# EasyEDA-SCH_IoT-Indoor-Climate-Sensor-up.net
KiCad netlist of a schematic drawn in EasyEDA
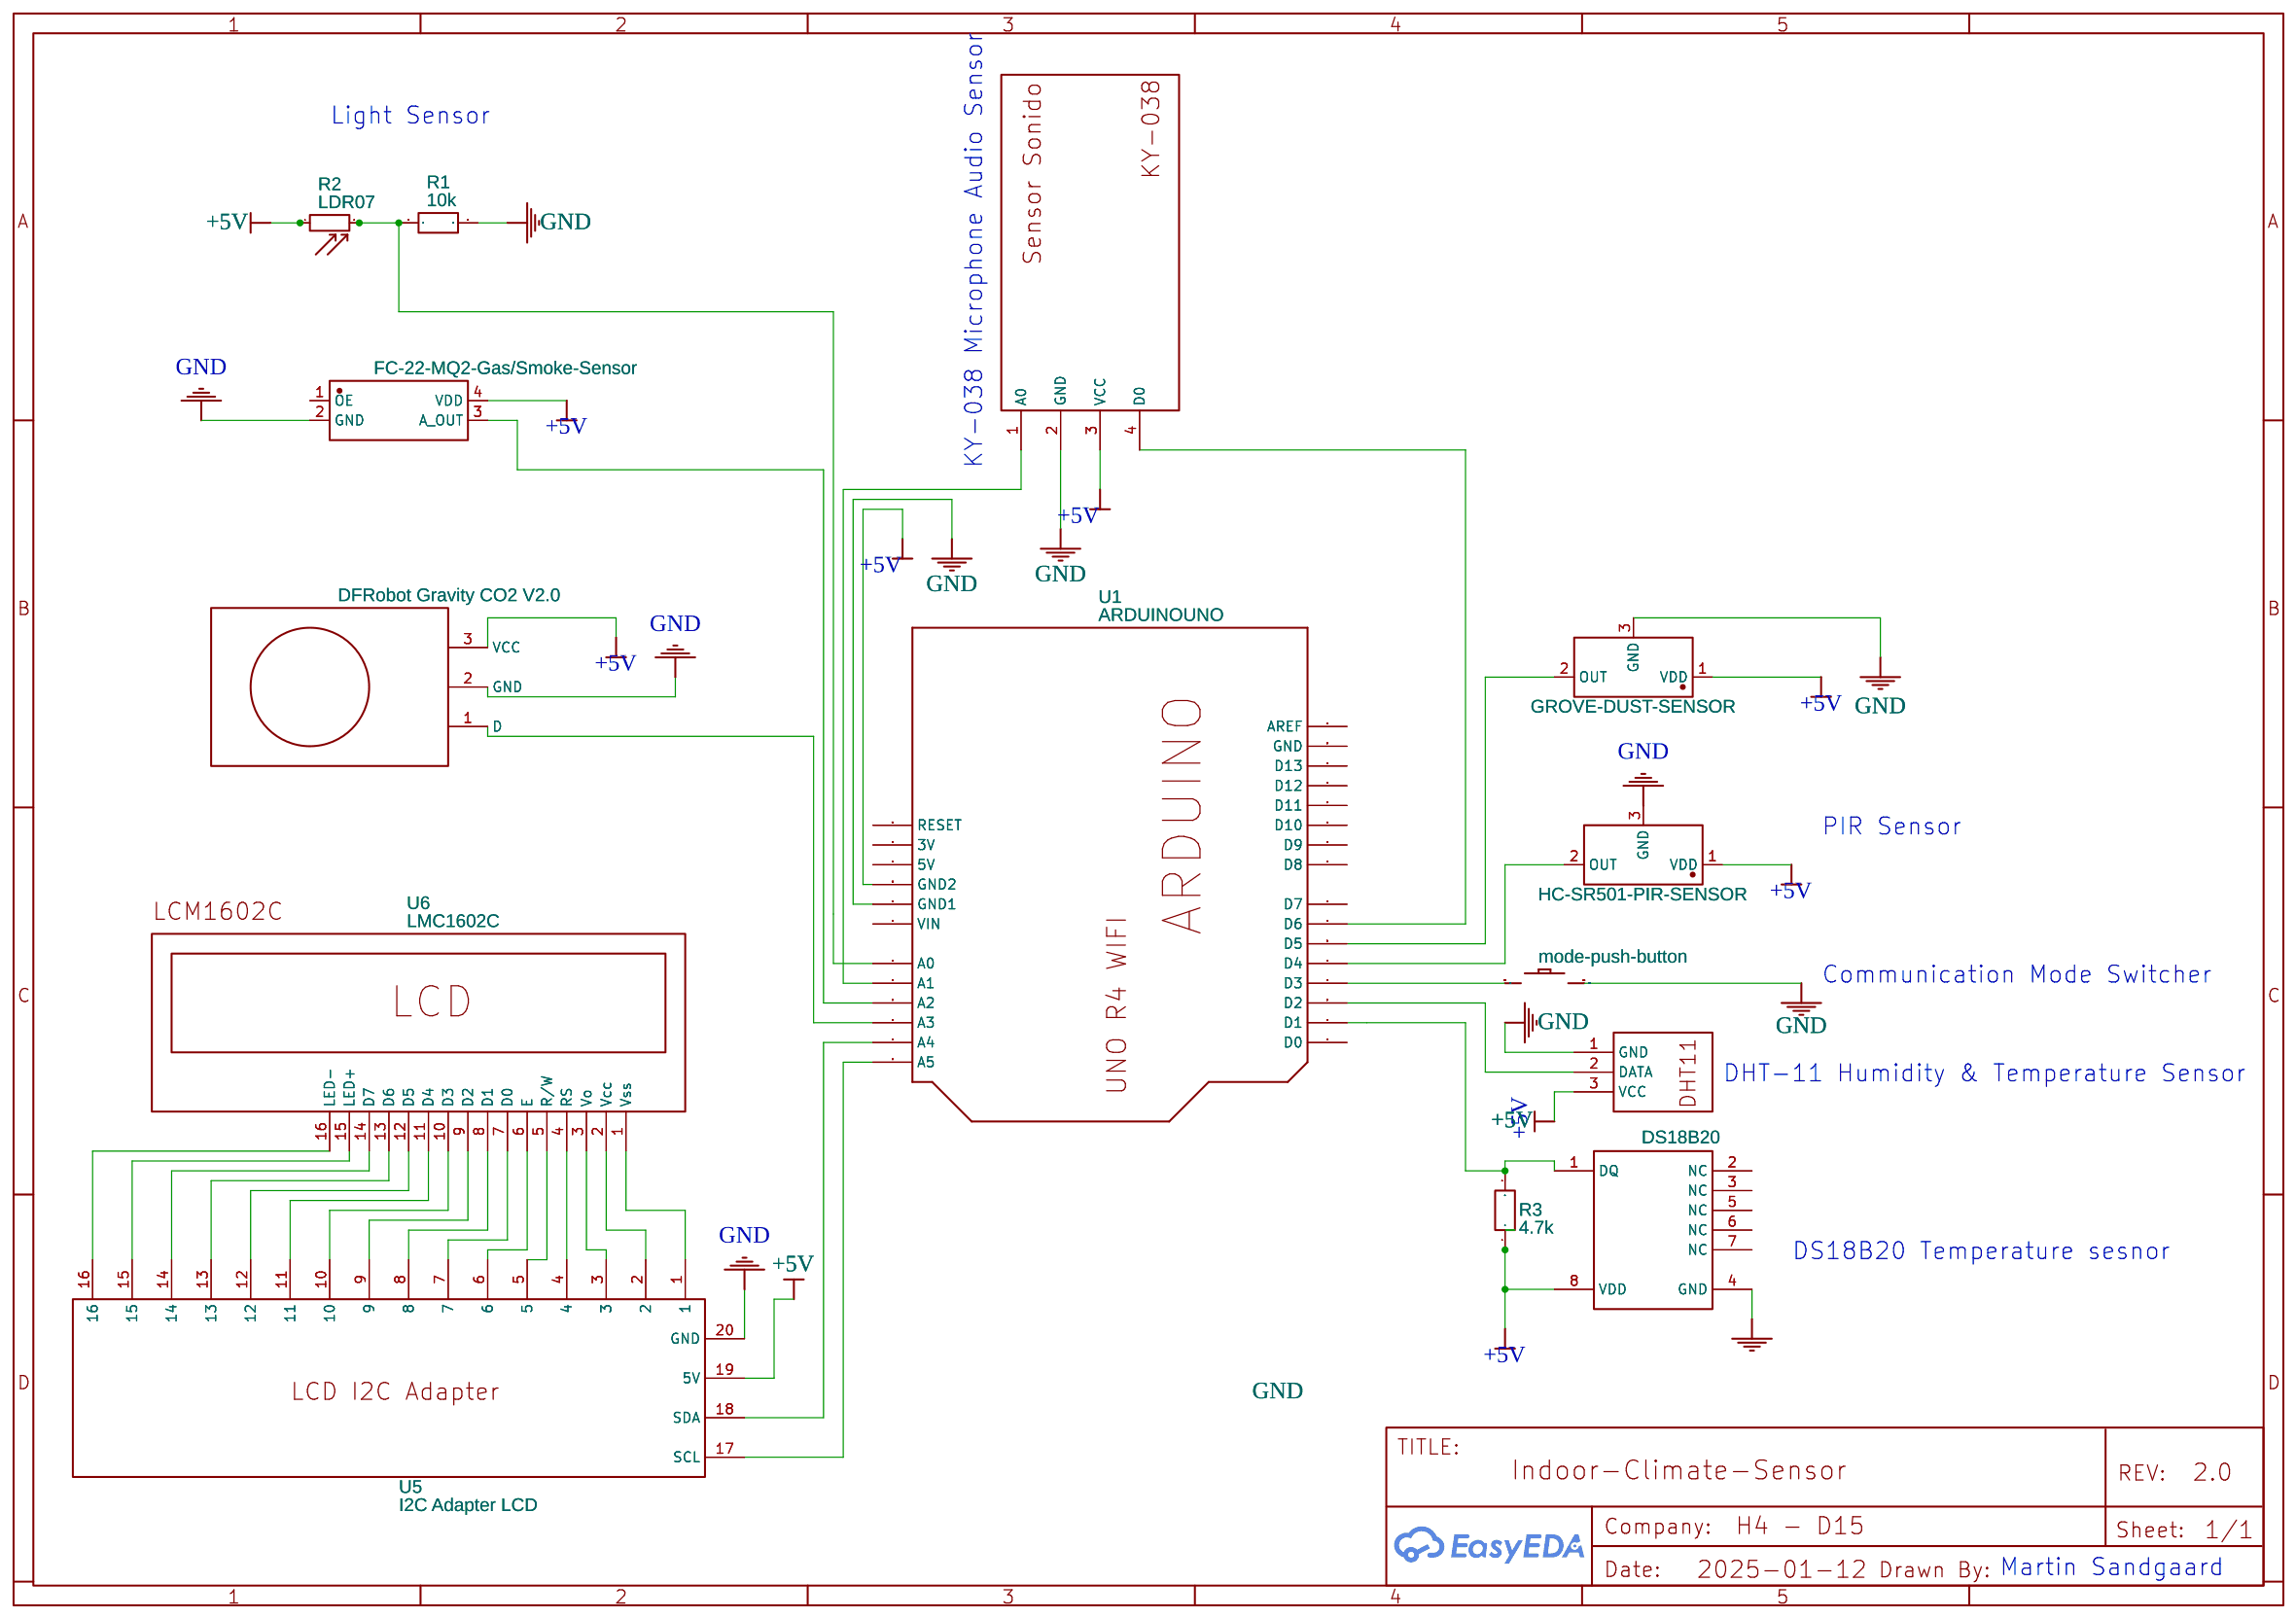
[diagram p0: schematic sheet]

(export (version "E")
  (design (tool "Eeschema 10.0.6"))
  (components
    (comp (ref "1") (value "mode-push-button") (libsource (lib "") (part "button")))
    (comp (ref "GROVE-DUST-SENSOR")
      (value "EKMB1309113K")
      (fields (field (name "Manufacturer") "PANASONIC(松下)"))
      (libsource (lib "") (part "EKMB1309113K_1"))
    )
    (comp (ref "HC-SR501-PIR-SENSOR")
      (value "EKMB1309113K")
      (fields (field (name "Manufacturer") "PANASONIC(松下)"))
      (libsource (lib "") (part "EKMB1309113K"))
    )
    (comp (ref "OSC1")
      (value "FC-22-MQ2-Gas/Smoke-Sensor")
      (fields (field (name "Manufacturer Part") "AMPMDFC-22.0000T3") (field (name "Manufacturer") "ABRACON"))
      (libsource (lib "") (part "AMPMDFC-22.0000T3"))
    )
    (comp (ref "R1") (value "10k") (libsource (lib "") (part "R_0603_EU_1")))
    (comp (ref "R2") (value "LDR07") (libsource (lib "") (part "LDR07")))
    (comp (ref "R3") (value "4.7k") (libsource (lib "") (part "R_0603_EU")))
    (comp (ref "U1") (value "ARDUINOUNO") (libsource (lib "") (part "ARDUINOUNO")))
    (comp (ref "U2") (value "DS18B20") (libsource (lib "") (part "DS18B20U+")))
    (comp (ref "U3")
      (value "KY-038 Microphone Sound Sensor")
      (libsource (lib "") (part "KY-037 KY038 SENSOR SONIDO COPY"))
    )
    (comp (ref "U4") (value "DHT-11") (libsource (lib "") (part "DHT-11")))
    (comp (ref "U5") (value "I2C Adapter LCD") (libsource (lib "") (part "I2C Adapter LCD")))
    (comp (ref "U6") (value "LMC1602C") (libsource (lib "") (part "LMC1602C")))
    (comp (ref "U7")
      (value "DFRobot Gravity CO2 V2.0")
      (libsource (lib "") (part "DFRobot Gravity - czujnik dwutlenku węgla CO2 - elektrochemiczny"))
    )
  )
  (nets
    (net (code "1") (name "+5V") (class "Default")
      (node (ref "GROVE-DUST-SENSOR") (pin "1") (pinfunction "VDD_1") (pintype "unspecified"))
      (node (ref "HC-SR501-PIR-SENSOR") (pin "1") (pinfunction "VDD_1") (pintype "unspecified"))
      (node (ref "OSC1") (pin "4") (pinfunction "VDD_4") (pintype "unspecified"))
      (node (ref "R2") (pin "1") (pintype "unspecified"))
      (node (ref "R3") (pin "1") (pinfunction "1_1") (pintype "unspecified"))
      (node (ref "U1") (pin "GND2") (pinfunction "GND2_GND2") (pintype "passive"))
      (node (ref "U2") (pin "8") (pinfunction "VDD_8") (pintype "passive"))
      (node (ref "U3") (pin "3") (pinfunction "VCC_3") (pintype "unspecified"))
      (node (ref "U4") (pin "3") (pinfunction "VCC_3") (pintype "unspecified"))
      (node (ref "U5") (pin "19") (pinfunction "5V_19") (pintype "unspecified"))
    )
    (net (code "2") (name "GND") (class "Default")
      (node (ref "1") (pin "P$ACTIVE") (pinfunction "P$ACTIVE_P$ACTIVE") (pintype "unspecified"))
      (node (ref "GROVE-DUST-SENSOR") (pin "3") (pinfunction "GND_3") (pintype "unspecified"))
      (node (ref "HC-SR501-PIR-SENSOR") (pin "3") (pinfunction "GND_3") (pintype "unspecified"))
      (node (ref "OSC1") (pin "2") (pinfunction "GND_2") (pintype "unspecified"))
      (node (ref "R1") (pin "1") (pinfunction "1_1") (pintype "unspecified"))
      (node (ref "U1") (pin "GND1") (pinfunction "GND1_GND1") (pintype "passive"))
      (node (ref "U2") (pin "4") (pinfunction "GND_4") (pintype "passive"))
      (node (ref "U3") (pin "2") (pinfunction "GND_2") (pintype "unspecified"))
      (node (ref "U4") (pin "1") (pinfunction "GND_1") (pintype "unspecified"))
      (node (ref "U5") (pin "20") (pinfunction "GND_20") (pintype "unspecified"))
    )
    (net (code "3") (name "Net-(1-PadP$GND)") (class "Default")
      (node (ref "1") (pin "P$GND") (pinfunction "P$GND_P$GND") (pintype "unspecified"))
      (node (ref "U1") (pin "D3") (pinfunction "D3_D3") (pintype "unspecified"))
    )
    (net (code "4") (name "Net-(GROVE-DUST-SENSOR-OUT)") (class "Default")
      (node (ref "GROVE-DUST-SENSOR") (pin "2") (pinfunction "OUT_2") (pintype "unspecified"))
      (node (ref "U1") (pin "D5") (pinfunction "D5_D5") (pintype "unspecified"))
    )
    (net (code "5") (name "Net-(HC-SR501-PIR-SENSOR-OUT)") (class "Default")
      (node (ref "HC-SR501-PIR-SENSOR") (pin "2") (pinfunction "OUT_2") (pintype "unspecified"))
      (node (ref "U1") (pin "D4") (pinfunction "D4_D4") (pintype "unspecified"))
    )
    (net (code "6") (name "Net-(OSC1-A_OUT)") (class "Default")
      (node (ref "OSC1") (pin "3") (pinfunction "A_OUT_3") (pintype "unspecified"))
      (node (ref "U1") (pin "A2") (pinfunction "A2_A2") (pintype "unspecified"))
    )
    (net (code "7") (name "Net-(R1-Pad2)") (class "Default")
      (node (ref "R1") (pin "2") (pinfunction "2_2") (pintype "unspecified"))
      (node (ref "R2") (pin "2") (pintype "unspecified"))
      (node (ref "U1") (pin "A0") (pinfunction "A0_A0") (pintype "unspecified"))
    )
    (net (code "8") (name "Net-(U2-DQ)") (class "Default")
      (node (ref "R3") (pin "2") (pinfunction "2_2") (pintype "unspecified"))
      (node (ref "U1") (pin "D1") (pinfunction "D1_D1") (pintype "unspecified"))
      (node (ref "U2") (pin "1") (pinfunction "DQ_1") (pintype "bidirectional"))
    )
    (net (code "9") (name "Net-(U3-A0)") (class "Default")
      (node (ref "U1") (pin "A1") (pinfunction "A1_A1") (pintype "unspecified"))
      (node (ref "U3") (pin "1") (pinfunction "A0_1") (pintype "unspecified"))
    )
    (net (code "10") (name "Net-(U3-D0)") (class "Default")
      (node (ref "U1") (pin "D6") (pinfunction "D6_D6") (pintype "unspecified"))
      (node (ref "U3") (pin "4") (pinfunction "D0_4") (pintype "unspecified"))
    )
    (net (code "11") (name "Net-(U4-DATA)") (class "Default")
      (node (ref "U1") (pin "D2") (pinfunction "D2_D2") (pintype "unspecified"))
      (node (ref "U4") (pin "2") (pinfunction "DATA_2") (pintype "unspecified"))
    )
    (net (code "12") (name "Net-(U5-SCL)") (class "Default")
      (node (ref "U1") (pin "A5") (pinfunction "A5_A5") (pintype "unspecified"))
      (node (ref "U5") (pin "17") (pinfunction "SCL_17") (pintype "unspecified"))
    )
    (net (code "13") (name "Net-(U5-SDA)") (class "Default")
      (node (ref "U1") (pin "A4") (pinfunction "A4_A4") (pintype "unspecified"))
      (node (ref "U5") (pin "18") (pinfunction "SDA_18") (pintype "unspecified"))
    )
    (net (code "14") (name "Net-(U6-D0)") (class "Default")
      (node (ref "U5") (pin "7") (pinfunction "7_7") (pintype "unspecified"))
      (node (ref "U6") (pin "7") (pinfunction "D0_7") (pintype "unspecified"))
    )
    (net (code "15") (name "Net-(U6-D1)") (class "Default")
      (node (ref "U5") (pin "8") (pinfunction "8_8") (pintype "unspecified"))
      (node (ref "U6") (pin "8") (pinfunction "D1_8") (pintype "unspecified"))
    )
    (net (code "16") (name "Net-(U6-D2)") (class "Default")
      (node (ref "U5") (pin "9") (pinfunction "9_9") (pintype "unspecified"))
      (node (ref "U6") (pin "9") (pinfunction "D2_9") (pintype "unspecified"))
    )
    (net (code "17") (name "Net-(U6-D3)") (class "Default")
      (node (ref "U5") (pin "10") (pinfunction "10_10") (pintype "unspecified"))
      (node (ref "U6") (pin "10") (pinfunction "D3_10") (pintype "unspecified"))
    )
    (net (code "18") (name "Net-(U6-D4)") (class "Default")
      (node (ref "U5") (pin "11") (pinfunction "11_11") (pintype "unspecified"))
      (node (ref "U6") (pin "11") (pinfunction "D4_11") (pintype "unspecified"))
    )
    (net (code "19") (name "Net-(U6-D5)") (class "Default")
      (node (ref "U5") (pin "12") (pinfunction "12_12") (pintype "unspecified"))
      (node (ref "U6") (pin "12") (pinfunction "D5_12") (pintype "unspecified"))
    )
    (net (code "20") (name "Net-(U6-D6)") (class "Default")
      (node (ref "U5") (pin "13") (pinfunction "13_13") (pintype "unspecified"))
      (node (ref "U6") (pin "13") (pinfunction "D6_13") (pintype "unspecified"))
    )
    (net (code "21") (name "Net-(U6-D7)") (class "Default")
      (node (ref "U5") (pin "14") (pinfunction "14_14") (pintype "unspecified"))
      (node (ref "U6") (pin "14") (pinfunction "D7_14") (pintype "unspecified"))
    )
    (net (code "22") (name "Net-(U6-E)") (class "Default")
      (node (ref "U5") (pin "6") (pinfunction "6_6") (pintype "unspecified"))
      (node (ref "U6") (pin "6") (pinfunction "E_6") (pintype "unspecified"))
    )
    (net (code "23") (name "Net-(U6-LED+)") (class "Default")
      (node (ref "U5") (pin "15") (pinfunction "15_15") (pintype "unspecified"))
      (node (ref "U6") (pin "15") (pinfunction "LED+_15") (pintype "unspecified"))
    )
    (net (code "24") (name "Net-(U6-LED-)") (class "Default")
      (node (ref "U5") (pin "16") (pinfunction "16_16") (pintype "unspecified"))
      (node (ref "U6") (pin "16") (pinfunction "LED-_16") (pintype "unspecified"))
    )
    (net (code "25") (name "Net-(U6-RS)") (class "Default")
      (node (ref "U5") (pin "4") (pinfunction "4_4") (pintype "unspecified"))
      (node (ref "U6") (pin "4") (pinfunction "RS_4") (pintype "unspecified"))
    )
    (net (code "26") (name "Net-(U6-R{slash}W)") (class "Default")
      (node (ref "U5") (pin "5") (pinfunction "5_5") (pintype "unspecified"))
      (node (ref "U6") (pin "5") (pinfunction "R/W_5") (pintype "unspecified"))
    )
    (net (code "27") (name "Net-(U6-Vcc)") (class "Default")
      (node (ref "U5") (pin "2") (pinfunction "2_2") (pintype "unspecified"))
      (node (ref "U6") (pin "2") (pinfunction "Vcc_2") (pintype "unspecified"))
    )
    (net (code "28") (name "Net-(U6-Vo)") (class "Default")
      (node (ref "U5") (pin "3") (pinfunction "3_3") (pintype "unspecified"))
      (node (ref "U6") (pin "3") (pinfunction "Vo_3") (pintype "unspecified"))
    )
    (net (code "29") (name "Net-(U6-Vss)") (class "Default")
      (node (ref "U5") (pin "1") (pinfunction "1_1") (pintype "unspecified"))
      (node (ref "U6") (pin "1") (pinfunction "Vss_1") (pintype "unspecified"))
    )
    (net (code "30") (name "unconnected-(OSC1-OE-Pad1)") (class "Default")
      (node (ref "OSC1") (pin "1") (pinfunction "OE_1") (pintype "unspecified"))
    )
    (net (code "31") (name "unconnected-(U1-Pad3V)") (class "Default")
      (node (ref "U1") (pin "3V") (pinfunction "3V_3V") (pintype "passive"))
    )
    (net (code "32") (name "unconnected-(U1-Pad5V)") (class "Default")
      (node (ref "U1") (pin "5V") (pinfunction "5V_5V") (pintype "passive"))
    )
    (net (code "33") (name "unconnected-(U1-PadA3)") (class "Default")
      (node (ref "U1") (pin "A3") (pinfunction "A3_A3") (pintype "unspecified"))
    )
    (net (code "34") (name "unconnected-(U1-PadAREF)") (class "Default")
      (node (ref "U1") (pin "AREF") (pinfunction "AREF_AREF") (pintype "unspecified"))
    )
    (net (code "35") (name "unconnected-(U1-PadD0)") (class "Default")
      (node (ref "U1") (pin "D0") (pinfunction "D0_D0") (pintype "unspecified"))
    )
    (net (code "36") (name "unconnected-(U1-PadD7)") (class "Default")
      (node (ref "U1") (pin "D7") (pinfunction "D7_D7") (pintype "unspecified"))
    )
    (net (code "37") (name "unconnected-(U1-PadD8)") (class "Default")
      (node (ref "U1") (pin "D8") (pinfunction "D8_D8") (pintype "unspecified"))
    )
    (net (code "38") (name "unconnected-(U1-PadD9)") (class "Default")
      (node (ref "U1") (pin "D9") (pinfunction "D9_D9") (pintype "unspecified"))
    )
    (net (code "39") (name "unconnected-(U1-PadD10)") (class "Default")
      (node (ref "U1") (pin "D10") (pinfunction "D10_D10") (pintype "unspecified"))
    )
    (net (code "40") (name "unconnected-(U1-PadD11)") (class "Default")
      (node (ref "U1") (pin "D11") (pinfunction "D11_D11") (pintype "unspecified"))
    )
    (net (code "41") (name "unconnected-(U1-PadD12)") (class "Default")
      (node (ref "U1") (pin "D12") (pinfunction "D12_D12") (pintype "unspecified"))
    )
    (net (code "42") (name "unconnected-(U1-PadD13)") (class "Default")
      (node (ref "U1") (pin "D13") (pinfunction "D13_D13") (pintype "unspecified"))
    )
    (net (code "43") (name "unconnected-(U1-PadGND)") (class "Default")
      (node (ref "U1") (pin "GND") (pinfunction "GND_GND") (pintype "passive"))
    )
    (net (code "44") (name "unconnected-(U1-PadRESET)") (class "Default")
      (node (ref "U1") (pin "RESET") (pinfunction "RESET_RESET") (pintype "unspecified"))
    )
    (net (code "45") (name "unconnected-(U1-PadVIN)") (class "Default")
      (node (ref "U1") (pin "VIN") (pinfunction "VIN_VIN") (pintype "passive"))
    )
    (net (code "46") (name "unconnected-(U2-NC-Pad2)") (class "Default")
      (node (ref "U2") (pin "2") (pinfunction "NC_2") (pintype "unspecified"))
    )
    (net (code "47") (name "unconnected-(U2-NC-Pad3)") (class "Default")
      (node (ref "U2") (pin "3") (pinfunction "NC_3") (pintype "unspecified"))
    )
    (net (code "48") (name "unconnected-(U2-NC-Pad5)") (class "Default")
      (node (ref "U2") (pin "5") (pinfunction "NC_5") (pintype "unspecified"))
    )
    (net (code "49") (name "unconnected-(U2-NC-Pad6)") (class "Default")
      (node (ref "U2") (pin "6") (pinfunction "NC_6") (pintype "unspecified"))
    )
    (net (code "50") (name "unconnected-(U2-NC-Pad7)") (class "Default")
      (node (ref "U2") (pin "7") (pinfunction "NC_7") (pintype "unspecified"))
    )
    (net (code "51") (name "unconnected-(U7-D-Pad1)") (class "Default")
      (node (ref "U7") (pin "1") (pinfunction "D_1") (pintype "unspecified"))
    )
    (net (code "52") (name "unconnected-(U7-GND-Pad2)") (class "Default")
      (node (ref "U7") (pin "2") (pinfunction "GND_2") (pintype "unspecified"))
    )
    (net (code "53") (name "unconnected-(U7-VCC-Pad3)") (class "Default")
      (node (ref "U7") (pin "3") (pinfunction "VCC_3") (pintype "unspecified"))
    )
  )
)
